# LDConnector_v3_-_CXY1.net
KiCad netlist of a schematic drawn in EAGLE
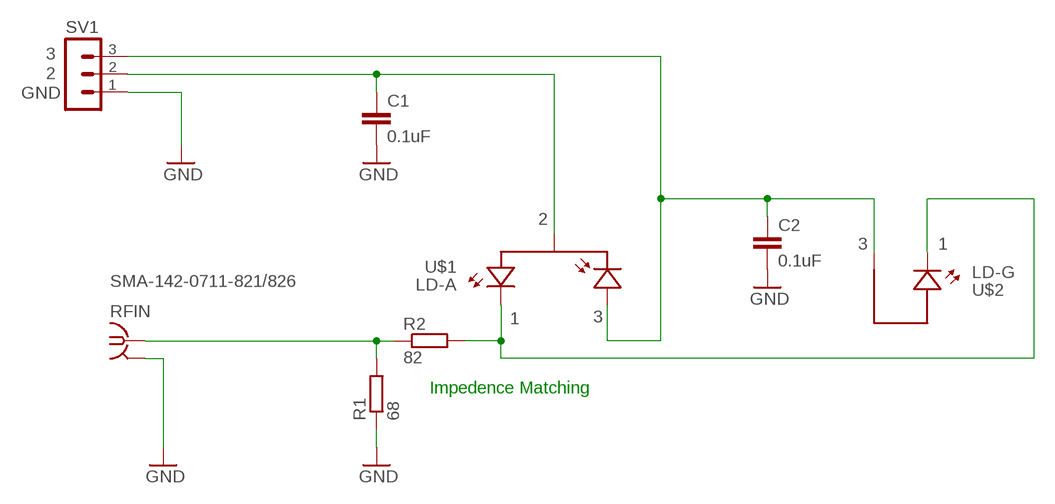
[diagram p0: schematic, sheet 1]

(export (version "E")
  (design (tool "Eeschema 10.0.6"))
  (components
    (comp (ref "C1")
      (value "0.1uF")
      (footprint "eagle-import:C0603")
      (libsource (lib "eagle-import") (part "C-EUC0603"))
    )
    (comp (ref "C2")
      (value "0.1uF")
      (footprint "eagle-import:C0603")
      (libsource (lib "eagle-import") (part "C-EUC0603"))
    )
    (comp (ref "R1")
      (value "68")
      (footprint "eagle-import:R0603")
      (libsource (lib "eagle-import") (part "R-EU_R0603"))
    )
    (comp (ref "R2")
      (value "82")
      (footprint "eagle-import:R0603")
      (libsource (lib "eagle-import") (part "R-EU_R0603"))
    )
    (comp (ref "RFIN")
      (value "SMA-142-0711-821/826")
      (footprint "eagle-import:J502-ND-142-0711-821_826")
      (fields (field (name "MF") "JOHNSON COMPONENTS") (field (name "MPN") "142-0711-821"))
      (libsource (lib "eagle-import") (part "SMA-142-0711-821/826"))
    )
    (comp (ref "SV1")
      (value "MA03-1")
      (footprint "eagle-import:MA03-1")
      (libsource (lib "eagle-import") (part "MA03-1"))
    )
    (comp (ref "U$1")
      (value "LD-A")
      (footprint "eagle-import:TYPEA")
      (libsource (lib "eagle-import") (part "LD-A"))
    )
    (comp (ref "U$2")
      (value "LD-G")
      (footprint "eagle-import:TYPEG")
      (libsource (lib "eagle-import") (part "LD-G"))
    )
  )
  (nets
    (net (code "1") (name "GND") (class "Default")
      (node (ref "C1") (pin "2") (pinfunction "2_2") (pintype "passive"))
      (node (ref "C2") (pin "2") (pinfunction "2_2") (pintype "passive"))
      (node (ref "R1") (pin "1") (pinfunction "1_1") (pintype "passive"))
      (node (ref "RFIN") (pin "G@1") (pinfunction "2_G@1") (pintype "passive"))
      (node (ref "RFIN") (pin "G@2") (pinfunction "2_G@2") (pintype "passive"))
      (node (ref "RFIN") (pin "G@3") (pinfunction "2_G@3") (pintype "passive"))
      (node (ref "RFIN") (pin "G@4") (pinfunction "2_G@4") (pintype "passive"))
      (node (ref "SV1") (pin "1") (pinfunction "1_1") (pintype "passive"))
    )
    (net (code "2") (name "Net-(R1-Pad2)") (class "Default")
      (node (ref "R1") (pin "2") (pinfunction "2_2") (pintype "passive"))
      (node (ref "R2") (pin "1") (pinfunction "1_1") (pintype "passive"))
      (node (ref "RFIN") (pin "1") (pinfunction "1_1") (pintype "passive"))
    )
    (net (code "3") (name "Net-(U$1-LDA-PDC)") (class "Default")
      (node (ref "C1") (pin "1") (pinfunction "1_1") (pintype "passive"))
      (node (ref "SV1") (pin "2") (pinfunction "2_2") (pintype "passive"))
      (node (ref "U$1") (pin "2-PDC-LDA") (pinfunction "LDA-PDC_2-PDC-LDA") (pintype "passive"))
    )
    (net (code "4") (name "Net-(U$1-LDC)") (class "Default")
      (node (ref "R2") (pin "2") (pinfunction "2_2") (pintype "passive"))
      (node (ref "U$1") (pin "1-LDC") (pinfunction "LDC_1-LDC") (pintype "passive"))
      (node (ref "U$2") (pin "1-LDC") (pinfunction "LDC_1-LDC") (pintype "passive"))
    )
    (net (code "5") (name "Net-(U$1-PDA)") (class "Default")
      (node (ref "C2") (pin "1") (pinfunction "1_1") (pintype "passive"))
      (node (ref "SV1") (pin "3") (pinfunction "3_3") (pintype "passive"))
      (node (ref "U$1") (pin "3-PDA") (pinfunction "PDA_3-PDA") (pintype "passive"))
      (node (ref "U$2") (pin "3-LDA") (pinfunction "LDA_3-LDA") (pintype "passive"))
    )
  )
)
